# LSM9DS0.net
KiCad netlist of a schematic drawn in Altium Designer
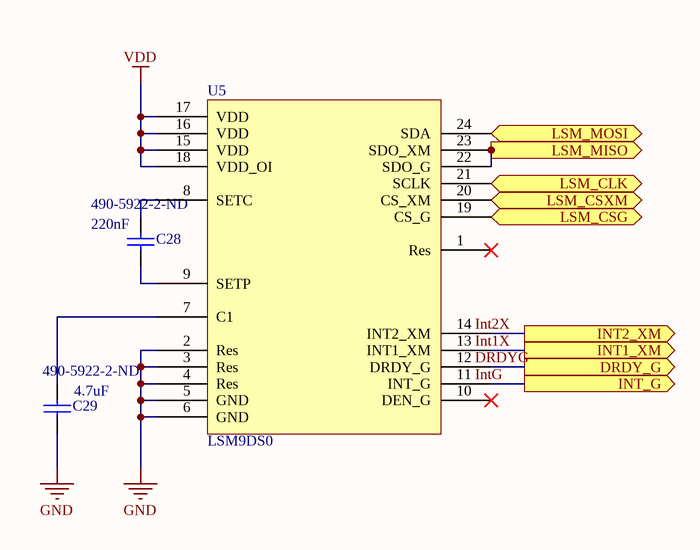
[diagram p0: LSM9DS0.SchDoc]

(export (version "E")
  (design (tool "Eeschema 10.0.6"))
  (components
    (comp (ref "C28")
      (value "220nF")
      (footprint "0402")
      (description "Capacitor (Semiconductor SIM Model)")
      (fields
        (field (name "SUPPLIER PART NUMBER 1") "490-5922-2-ND")
        (field (name "Comment") "Cap Semi")
        (field (name "PUBLISHER") "Altium Limited")
      )
      (libsource (lib "Miscellaneous Devices") (part "Cap Semi"))
    )
    (comp (ref "C29")
      (value "4.7uF")
      (footprint "0402")
      (description "Capacitor (Semiconductor SIM Model)")
      (fields
        (field (name "SUPPLIER PART NUMBER 1") "490-5922-2-ND")
        (field (name "Comment") "Cap Semi")
        (field (name "PUBLISHER") "Altium Limited")
      )
      (libsource (lib "Miscellaneous Devices") (part "Cap Semi"))
    )
    (comp (ref "U5")
      (value "Component_1")
      (footprint "PCBComponent_1")
      (libsource (lib "LSM9DS0") (part "Component_1"))
    )
  )
  (nets
    (net (code "2") (name "/DRDY_G") (class "Default")
      (node (ref "U5") (pin "12") (pinfunction "DRDY_G_12") (pintype "passive"))
    )
    (net (code "3") (name "/INT1_XM") (class "Default")
      (node (ref "U5") (pin "13") (pinfunction "INT1_XM_13") (pintype "passive"))
    )
    (net (code "4") (name "/INT2_XM") (class "Default")
      (node (ref "U5") (pin "14") (pinfunction "INT2_XM_14") (pintype "passive"))
    )
    (net (code "5") (name "/INT_G") (class "Default")
      (node (ref "U5") (pin "11") (pinfunction "INT_G_11") (pintype "passive"))
    )
    (net (code "9") (name "/LSM_CLK") (class "Default")
      (node (ref "U5") (pin "21") (pinfunction "SCLK_21") (pintype "passive"))
    )
    (net (code "10") (name "/LSM_CSG") (class "Default")
      (node (ref "U5") (pin "19") (pinfunction "CS_G_19") (pintype "passive"))
    )
    (net (code "11") (name "/LSM_CSXM") (class "Default")
      (node (ref "U5") (pin "20") (pinfunction "CS_XM_20") (pintype "passive"))
    )
    (net (code "12") (name "/LSM_MISO") (class "Default")
      (node (ref "U5") (pin "22") (pinfunction "SDO_G_22") (pintype "passive"))
      (node (ref "U5") (pin "23") (pinfunction "SDO_XM_23") (pintype "passive"))
    )
    (net (code "13") (name "/LSM_MOSI") (class "Default")
      (node (ref "U5") (pin "24") (pinfunction "SDA_24") (pintype "passive"))
    )
    (net (code "14") (name "GND") (class "Default")
      (node (ref "C29") (pin "1") (pinfunction "1_1") (pintype "passive"))
      (node (ref "U5") (pin "2") (pinfunction "Res_2") (pintype "passive"))
      (node (ref "U5") (pin "3") (pinfunction "Res_3") (pintype "passive"))
      (node (ref "U5") (pin "4") (pinfunction "Res_4") (pintype "passive"))
      (node (ref "U5") (pin "5") (pinfunction "GND_5") (pintype "passive"))
      (node (ref "U5") (pin "6") (pinfunction "GND_6") (pintype "passive"))
    )
    (net (code "15") (name "Net-(U5-C1)") (class "Default")
      (node (ref "C29") (pin "2") (pinfunction "2_2") (pintype "passive"))
      (node (ref "U5") (pin "7") (pinfunction "C1_7") (pintype "passive"))
    )
    (net (code "16") (name "Net-(U5-SETC)") (class "Default")
      (node (ref "C28") (pin "2") (pinfunction "2_2") (pintype "passive"))
      (node (ref "U5") (pin "8") (pinfunction "SETC_8") (pintype "passive"))
    )
    (net (code "17") (name "Net-(U5-SETP)") (class "Default")
      (node (ref "C28") (pin "1") (pinfunction "1_1") (pintype "passive"))
      (node (ref "U5") (pin "9") (pinfunction "SETP_9") (pintype "passive"))
    )
    (net (code "18") (name "VDD") (class "Default")
      (node (ref "U5") (pin "15") (pinfunction "VDD_15") (pintype "passive"))
      (node (ref "U5") (pin "16") (pinfunction "VDD_16") (pintype "passive"))
      (node (ref "U5") (pin "17") (pinfunction "VDD_17") (pintype "passive"))
      (node (ref "U5") (pin "18") (pinfunction "VDD_OI_18") (pintype "passive"))
    )
    (net (code "19") (name "unconnected-(U5-DEN_G-Pad10)") (class "Default")
      (node (ref "U5") (pin "10") (pinfunction "DEN_G_10") (pintype "passive+no_connect"))
    )
    (net (code "20") (name "unconnected-(U5-Res-Pad1)") (class "Default")
      (node (ref "U5") (pin "1") (pinfunction "Res_1") (pintype "passive+no_connect"))
    )
  )
)
